# drum_circuits.net
KiCad netlist of a schematic drawn in EAGLE
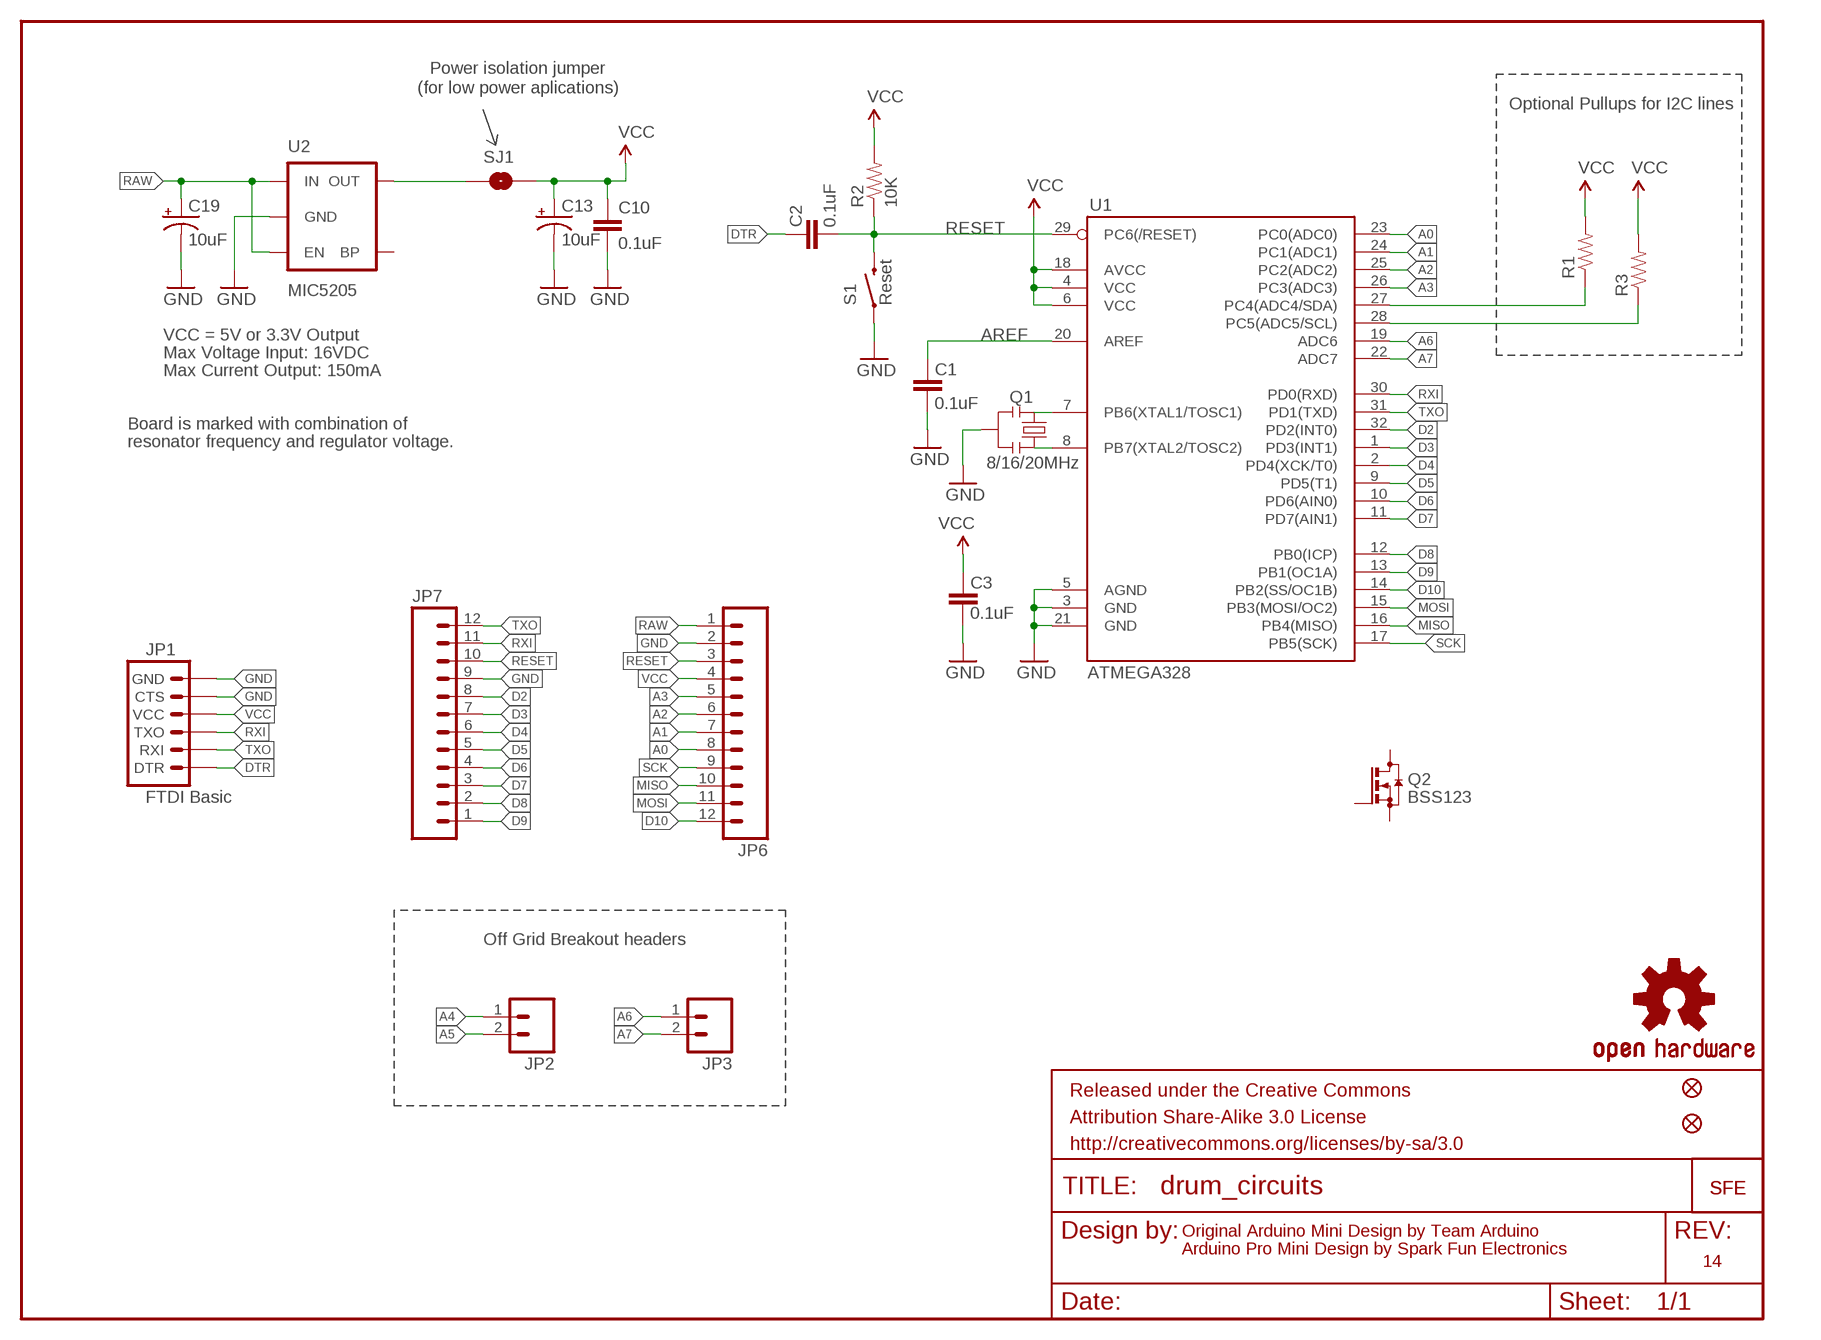
[diagram p0: schematic, sheet 1]

(export (version "E")
  (design (tool "Eeschema 10.0.6"))
  (components
    (comp (ref "C1")
      (value "0.1uF")
      (footprint "eagle-import:0603-CAP")
      (libsource (lib "eagle-import") (part "CAP0603-CAP"))
    )
    (comp (ref "C2")
      (value "0.1uF")
      (footprint "eagle-import:0603-CAP")
      (libsource (lib "eagle-import") (part "CAP0603-CAP"))
    )
    (comp (ref "C3")
      (value "0.1uF")
      (footprint "eagle-import:0603-CAP")
      (libsource (lib "eagle-import") (part "CAP0603-CAP"))
    )
    (comp (ref "C10")
      (value "0.1uF")
      (footprint "eagle-import:0603-CAP")
      (libsource (lib "eagle-import") (part "CAP0603-CAP"))
    )
    (comp (ref "C13")
      (value "10uF")
      (footprint "eagle-import:EIA3216")
      (libsource (lib "eagle-import") (part "CAP_POL1206"))
    )
    (comp (ref "C19")
      (value "10uF")
      (footprint "eagle-import:EIA3216")
      (libsource (lib "eagle-import") (part "CAP_POL1206"))
    )
    (comp (ref "FRAME1")
      (value "FRAME-LETTER")
      (footprint "eagle-import:CREATIVE_COMMONS")
      (libsource (lib "eagle-import") (part "FRAME-LETTER"))
    )
    (comp (ref "JP1")
      (value "FTDI Basic")
      (footprint "eagle-import:1X06")
      (libsource (lib "eagle-import") (part "ARDUINO_SERIAL_PROGRAMPTH"))
    )
    (comp (ref "JP2")
      (value "M02PTH")
      (footprint "eagle-import:1X02")
      (libsource (lib "eagle-import") (part "M02PTH"))
    )
    (comp (ref "JP3")
      (value "M02PTH")
      (footprint "eagle-import:1X02")
      (libsource (lib "eagle-import") (part "M02PTH"))
    )
    (comp (ref "JP5")
      (value "FIDUCIALUFIDUCIAL")
      (footprint "eagle-import:MICRO-FIDUCIAL")
      (libsource (lib "eagle-import") (part "FIDUCIALUFIDUCIAL"))
    )
    (comp (ref "JP6")
      (value "M12PTH")
      (footprint "eagle-import:1X12")
      (libsource (lib "eagle-import") (part "M12PTH"))
    )
    (comp (ref "JP7")
      (value "M12PTH")
      (footprint "eagle-import:1X12")
      (libsource (lib "eagle-import") (part "M12PTH"))
    )
    (comp (ref "JP8")
      (value "FIDUCIALUFIDUCIAL")
      (footprint "eagle-import:MICRO-FIDUCIAL")
      (libsource (lib "eagle-import") (part "FIDUCIALUFIDUCIAL"))
    )
    (comp (ref "Q1")
      (value "8/16/20MHz")
      (footprint "eagle-import:RESONATOR-SMD-1_1")
      (libsource (lib "eagle-import") (part "RESONATOR1{colon}1"))
    )
    (comp (ref "Q2")
      (value "BSS123")
      (footprint "eagle-import:SOT23")
      (libsource (lib "eagle-import") (part "BSS123"))
    )
    (comp (ref "R1")
      (value "RESISTOR0603-RES")
      (footprint "eagle-import:0603-RES")
      (libsource (lib "eagle-import") (part "RESISTOR0603-RES"))
    )
    (comp (ref "R2")
      (value "10K")
      (footprint "eagle-import:0603-RES")
      (libsource (lib "eagle-import") (part "RESISTOR0603-RES"))
    )
    (comp (ref "R3")
      (value "RESISTOR0603-RES")
      (footprint "eagle-import:0603-RES")
      (libsource (lib "eagle-import") (part "RESISTOR0603-RES"))
    )
    (comp (ref "S1")
      (value "Reset")
      (footprint "eagle-import:TACTILE-SWITCH-SMD-ALT01")
      (libsource (lib "eagle-import") (part "SWITCH-MOMENTARY-2SMD-ALT01"))
    )
    (comp (ref "SJ1")
      (value "SOLDERJUMPERNC")
      (footprint "eagle-import:SJ_2S")
      (libsource (lib "eagle-import") (part "SOLDERJUMPERNC"))
    )
    (comp (ref "U$1")
      (value "LOGO-SFESK")
      (footprint "eagle-import:SFE-LOGO-FLAME")
      (libsource (lib "eagle-import") (part "LOGO-SFESK"))
    )
    (comp (ref "U$3")
      (value "OSHW-LOGOS")
      (footprint "eagle-import:OSHW-LOGO-S")
      (libsource (lib "eagle-import") (part "OSHW-LOGOS"))
    )
    (comp (ref "U$11")
      (value "LOGO-SFENEW")
      (footprint "eagle-import:SFE-NEW-WEBLOGO")
      (libsource (lib "eagle-import") (part "LOGO-SFENEW"))
    )
    (comp (ref "U1")
      (value "ATMEGA328")
      (footprint "eagle-import:TQFP32-08")
      (libsource (lib "eagle-import") (part "ATMEGA168"))
    )
    (comp (ref "U2")
      (value "MIC5205")
      (footprint "eagle-import:SOT23-5")
      (libsource (lib "eagle-import") (part "V_REG_LDOSMD"))
    )
  )
  (nets
    (net (code "1") (name "/AREF") (class "Default")
      (node (ref "C1") (pin "2") (pinfunction "2_2") (pintype "passive"))
      (node (ref "U1") (pin "20") (pinfunction "AREF_20") (pintype "bidirectional"))
    )
    (net (code "2") (name "A0") (class "Default")
      (node (ref "JP6") (pin "8") (pinfunction "8_8") (pintype "passive"))
      (node (ref "U1") (pin "23") (pinfunction "PC0(ADC0)_23") (pintype "bidirectional"))
    )
    (net (code "3") (name "A1") (class "Default")
      (node (ref "JP6") (pin "7") (pinfunction "7_7") (pintype "passive"))
      (node (ref "U1") (pin "24") (pinfunction "PC1(ADC1)_24") (pintype "bidirectional"))
    )
    (net (code "4") (name "A2") (class "Default")
      (node (ref "JP6") (pin "6") (pinfunction "6_6") (pintype "passive"))
      (node (ref "U1") (pin "25") (pinfunction "PC2(ADC2)_25") (pintype "bidirectional"))
    )
    (net (code "5") (name "A3") (class "Default")
      (node (ref "JP6") (pin "5") (pinfunction "5_5") (pintype "passive"))
      (node (ref "U1") (pin "26") (pinfunction "PC3(ADC3)_26") (pintype "bidirectional"))
    )
    (net (code "6") (name "A4") (class "Default")
      (node (ref "JP2") (pin "1") (pinfunction "1_1") (pintype "passive"))
      (node (ref "R1") (pin "1") (pinfunction "1_1") (pintype "passive"))
      (node (ref "U1") (pin "27") (pinfunction "PC4(ADC4/SDA)_27") (pintype "bidirectional"))
    )
    (net (code "7") (name "A5") (class "Default")
      (node (ref "JP2") (pin "2") (pinfunction "2_2") (pintype "passive"))
      (node (ref "R3") (pin "1") (pinfunction "1_1") (pintype "passive"))
      (node (ref "U1") (pin "28") (pinfunction "PC5(ADC5/SCL)_28") (pintype "bidirectional"))
    )
    (net (code "8") (name "A6") (class "Default")
      (node (ref "JP3") (pin "1") (pinfunction "1_1") (pintype "passive"))
      (node (ref "U1") (pin "19") (pinfunction "ADC6_19") (pintype "bidirectional"))
    )
    (net (code "9") (name "A7") (class "Default")
      (node (ref "JP3") (pin "2") (pinfunction "2_2") (pintype "passive"))
      (node (ref "U1") (pin "22") (pinfunction "ADC7_22") (pintype "bidirectional"))
    )
    (net (code "10") (name "D2") (class "Default")
      (node (ref "JP7") (pin "8") (pinfunction "8_8") (pintype "passive"))
      (node (ref "U1") (pin "32") (pinfunction "PD2(INT0)_32") (pintype "bidirectional"))
    )
    (net (code "11") (name "D3") (class "Default")
      (node (ref "JP7") (pin "7") (pinfunction "7_7") (pintype "passive"))
      (node (ref "U1") (pin "1") (pinfunction "PD3(INT1)_1") (pintype "bidirectional"))
    )
    (net (code "12") (name "D4") (class "Default")
      (node (ref "JP7") (pin "6") (pinfunction "6_6") (pintype "passive"))
      (node (ref "U1") (pin "2") (pinfunction "PD4(XCK/T0)_2") (pintype "bidirectional"))
    )
    (net (code "13") (name "D5") (class "Default")
      (node (ref "JP7") (pin "5") (pinfunction "5_5") (pintype "passive"))
      (node (ref "U1") (pin "9") (pinfunction "PD5(T1)_9") (pintype "bidirectional"))
    )
    (net (code "14") (name "D6") (class "Default")
      (node (ref "JP7") (pin "4") (pinfunction "4_4") (pintype "passive"))
      (node (ref "U1") (pin "10") (pinfunction "PD6(AIN0)_10") (pintype "bidirectional"))
    )
    (net (code "15") (name "D7") (class "Default")
      (node (ref "JP7") (pin "3") (pinfunction "3_3") (pintype "passive"))
      (node (ref "U1") (pin "11") (pinfunction "PD7(AIN1)_11") (pintype "bidirectional"))
    )
    (net (code "16") (name "D8") (class "Default")
      (node (ref "JP7") (pin "2") (pinfunction "2_2") (pintype "passive"))
      (node (ref "U1") (pin "12") (pinfunction "PB0(ICP)_12") (pintype "bidirectional"))
    )
    (net (code "17") (name "D9") (class "Default")
      (node (ref "JP7") (pin "1") (pinfunction "1_1") (pintype "passive"))
      (node (ref "U1") (pin "13") (pinfunction "PB1(OC1A)_13") (pintype "bidirectional"))
    )
    (net (code "18") (name "D10") (class "Default")
      (node (ref "JP6") (pin "12") (pinfunction "12_12") (pintype "passive"))
      (node (ref "U1") (pin "14") (pinfunction "PB2(SS/OC1B)_14") (pintype "bidirectional"))
    )
    (net (code "19") (name "DTR") (class "Default")
      (node (ref "C2") (pin "2") (pinfunction "2_2") (pintype "passive"))
      (node (ref "JP1") (pin "1") (pinfunction "DTR_1") (pintype "passive"))
    )
    (net (code "20") (name "GND") (class "Default")
      (node (ref "C1") (pin "1") (pinfunction "1_1") (pintype "passive"))
      (node (ref "C10") (pin "2") (pinfunction "2_2") (pintype "passive"))
      (node (ref "C13") (pin "C") (pinfunction "-_C") (pintype "passive"))
      (node (ref "C19") (pin "C") (pinfunction "-_C") (pintype "passive"))
      (node (ref "C3") (pin "1") (pinfunction "1_1") (pintype "passive"))
      (node (ref "JP1") (pin "5") (pinfunction "CTS_5") (pintype "passive"))
      (node (ref "JP1") (pin "6") (pinfunction "GND_6") (pintype "passive"))
      (node (ref "JP6") (pin "2") (pinfunction "2_2") (pintype "passive"))
      (node (ref "JP7") (pin "9") (pinfunction "9_9") (pintype "passive"))
      (node (ref "Q1") (pin "2") (pinfunction "2_2") (pintype "passive"))
      (node (ref "S1") (pin "1") (pinfunction "1_1") (pintype "passive"))
      (node (ref "S1") (pin "2") (pinfunction "1_2") (pintype "passive"))
      (node (ref "U1") (pin "21") (pinfunction "GND_21") (pintype "bidirectional"))
      (node (ref "U1") (pin "3") (pinfunction "GND_3") (pintype "bidirectional"))
      (node (ref "U1") (pin "5") (pinfunction "AGND_5") (pintype "bidirectional"))
      (node (ref "U2") (pin "2") (pinfunction "GND_2") (pintype "input"))
    )
    (net (code "21") (name "MISO") (class "Default")
      (node (ref "JP6") (pin "10") (pinfunction "10_10") (pintype "passive"))
      (node (ref "U1") (pin "16") (pinfunction "PB4(MISO)_16") (pintype "bidirectional"))
    )
    (net (code "22") (name "MOSI") (class "Default")
      (node (ref "JP6") (pin "11") (pinfunction "11_11") (pintype "passive"))
      (node (ref "U1") (pin "15") (pinfunction "PB3(MOSI/OC2)_15") (pintype "bidirectional"))
    )
    (net (code "23") (name "Net-(U1-PB6(XTAL1{slash}TOSC1))") (class "Default")
      (node (ref "Q1") (pin "1") (pinfunction "1_1") (pintype "passive"))
      (node (ref "U1") (pin "7") (pinfunction "PB6(XTAL1/TOSC1)_7") (pintype "bidirectional"))
    )
    (net (code "24") (name "Net-(U1-PB7(XTAL2{slash}TOSC2))") (class "Default")
      (node (ref "Q1") (pin "3") (pinfunction "3_3") (pintype "passive"))
      (node (ref "U1") (pin "8") (pinfunction "PB7(XTAL2/TOSC2)_8") (pintype "bidirectional"))
    )
    (net (code "25") (name "Net-(U2-OUT)") (class "Default")
      (node (ref "SJ1") (pin "1") (pinfunction "1_1") (pintype "passive"))
      (node (ref "U2") (pin "5") (pinfunction "OUT_5") (pintype "passive"))
    )
    (net (code "26") (name "RAW") (class "Default")
      (node (ref "C19") (pin "A") (pinfunction "+_A") (pintype "passive"))
      (node (ref "JP6") (pin "1") (pinfunction "1_1") (pintype "passive"))
      (node (ref "U2") (pin "1") (pinfunction "IN_1") (pintype "input"))
      (node (ref "U2") (pin "3") (pinfunction "EN_3") (pintype "input"))
    )
    (net (code "27") (name "RESET") (class "Default")
      (node (ref "C2") (pin "1") (pinfunction "1_1") (pintype "passive"))
      (node (ref "JP6") (pin "3") (pinfunction "3_3") (pintype "passive"))
      (node (ref "JP7") (pin "10") (pinfunction "10_10") (pintype "passive"))
      (node (ref "R2") (pin "1") (pinfunction "1_1") (pintype "passive"))
      (node (ref "S1") (pin "3") (pinfunction "2_3") (pintype "passive"))
      (node (ref "S1") (pin "4") (pinfunction "2_4") (pintype "passive"))
      (node (ref "U1") (pin "29") (pinfunction "PC6(/RESET)_29") (pintype "bidirectional"))
    )
    (net (code "28") (name "RXI") (class "Default")
      (node (ref "JP1") (pin "3") (pinfunction "TXO_3") (pintype "passive"))
      (node (ref "JP7") (pin "11") (pinfunction "11_11") (pintype "passive"))
      (node (ref "U1") (pin "30") (pinfunction "PD0(RXD)_30") (pintype "bidirectional"))
    )
    (net (code "29") (name "SCK") (class "Default")
      (node (ref "JP6") (pin "9") (pinfunction "9_9") (pintype "passive"))
      (node (ref "U1") (pin "17") (pinfunction "PB5(SCK)_17") (pintype "bidirectional"))
    )
    (net (code "30") (name "TXO") (class "Default")
      (node (ref "JP1") (pin "2") (pinfunction "RXI_2") (pintype "passive"))
      (node (ref "JP7") (pin "12") (pinfunction "12_12") (pintype "passive"))
      (node (ref "U1") (pin "31") (pinfunction "PD1(TXD)_31") (pintype "bidirectional"))
    )
    (net (code "31") (name "VCC") (class "Default")
      (node (ref "C10") (pin "1") (pinfunction "1_1") (pintype "passive"))
      (node (ref "C13") (pin "A") (pinfunction "+_A") (pintype "passive"))
      (node (ref "C3") (pin "2") (pinfunction "2_2") (pintype "passive"))
      (node (ref "JP1") (pin "4") (pinfunction "VCC_4") (pintype "passive"))
      (node (ref "JP6") (pin "4") (pinfunction "4_4") (pintype "passive"))
      (node (ref "R1") (pin "2") (pinfunction "2_2") (pintype "passive"))
      (node (ref "R2") (pin "2") (pinfunction "2_2") (pintype "passive"))
      (node (ref "R3") (pin "2") (pinfunction "2_2") (pintype "passive"))
      (node (ref "SJ1") (pin "2") (pinfunction "2_2") (pintype "passive"))
      (node (ref "U1") (pin "18") (pinfunction "AVCC_18") (pintype "bidirectional"))
      (node (ref "U1") (pin "4") (pinfunction "VCC_4") (pintype "bidirectional"))
      (node (ref "U1") (pin "6") (pinfunction "VCC_6") (pintype "bidirectional"))
    )
    (net (code "32") (name "unconnected-(Q2-D-Pad3)") (class "Default")
      (node (ref "Q2") (pin "3") (pinfunction "D_3") (pintype "passive"))
    )
    (net (code "33") (name "unconnected-(Q2-G-Pad1)") (class "Default")
      (node (ref "Q2") (pin "1") (pinfunction "G_1") (pintype "passive"))
    )
    (net (code "34") (name "unconnected-(Q2-S-Pad2)") (class "Default")
      (node (ref "Q2") (pin "2") (pinfunction "S_2") (pintype "passive"))
    )
    (net (code "35") (name "unconnected-(U2-BP-Pad4)") (class "Default")
      (node (ref "U2") (pin "4") (pinfunction "BP_4") (pintype "input"))
    )
  )
)
